# 2015_CONNECTEUR_BALISE.net
KiCad netlist of a schematic drawn in Altium Designer
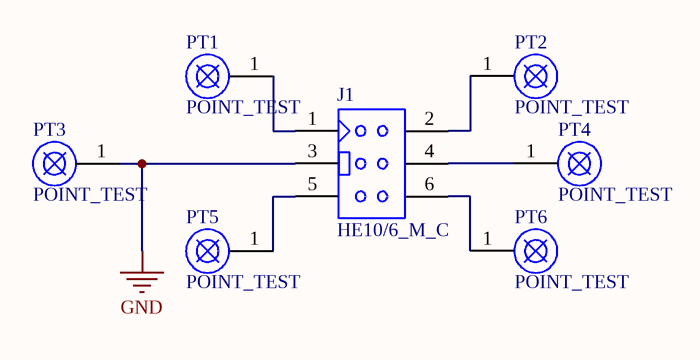
[diagram p0: 2015_CONNECTEUR_BALISE.SchDoc]

(export (version "E")
  (design (tool "Eeschema 10.0.6"))
  (components
    (comp (ref "J1")
      (value "HE10/6_MALE_COUDE")
      (footprint "HE10/6_M_C")
      (description "EMBASE HE10/6 MALE COUDE")
      (fields (field (name "TYPE") "HE10/6_M_C"))
      (libsource (lib "connecteurs") (part "HE10/6_MALE_COUDE"))
    )
    (comp (ref "PT1")
      (value "POINT_TEST")
      (footprint "POINT_TEST")
      (description "POINT TEST")
      (libsource (lib "connecteurs") (part "POINT_TEST"))
    )
    (comp (ref "PT2")
      (value "POINT_TEST")
      (footprint "POINT_TEST")
      (description "POINT TEST")
      (libsource (lib "connecteurs") (part "POINT_TEST"))
    )
    (comp (ref "PT3")
      (value "POINT_TEST")
      (footprint "POINT_TEST")
      (description "POINT TEST")
      (libsource (lib "connecteurs") (part "POINT_TEST"))
    )
    (comp (ref "PT4")
      (value "POINT_TEST")
      (footprint "POINT_TEST")
      (description "POINT TEST")
      (libsource (lib "connecteurs") (part "POINT_TEST"))
    )
    (comp (ref "PT5")
      (value "POINT_TEST")
      (footprint "POINT_TEST")
      (description "POINT TEST")
      (libsource (lib "connecteurs") (part "POINT_TEST"))
    )
    (comp (ref "PT6")
      (value "POINT_TEST")
      (footprint "POINT_TEST")
      (description "POINT TEST")
      (libsource (lib "connecteurs") (part "POINT_TEST"))
    )
  )
  (nets
    (net (code "1") (name "GND") (class "Default")
      (node (ref "J1") (pin "3") (pinfunction "3_3") (pintype "passive"))
      (node (ref "PT3") (pin "1") (pinfunction "3_1") (pintype "passive"))
    )
    (net (code "2") (name "Net-(PT1-3)") (class "Default")
      (node (ref "J1") (pin "1") (pinfunction "1_1") (pintype "passive"))
      (node (ref "PT1") (pin "1") (pinfunction "3_1") (pintype "passive"))
    )
    (net (code "3") (name "Net-(PT2-3)") (class "Default")
      (node (ref "J1") (pin "2") (pinfunction "2_2") (pintype "passive"))
      (node (ref "PT2") (pin "1") (pinfunction "3_1") (pintype "passive"))
    )
    (net (code "4") (name "Net-(PT4-3)") (class "Default")
      (node (ref "J1") (pin "4") (pinfunction "4_4") (pintype "passive"))
      (node (ref "PT4") (pin "1") (pinfunction "3_1") (pintype "passive"))
    )
    (net (code "5") (name "Net-(PT5-3)") (class "Default")
      (node (ref "J1") (pin "5") (pinfunction "5_5") (pintype "passive"))
      (node (ref "PT5") (pin "1") (pinfunction "3_1") (pintype "passive"))
    )
    (net (code "6") (name "Net-(PT6-3)") (class "Default")
      (node (ref "J1") (pin "6") (pinfunction "6_6") (pintype "passive"))
      (node (ref "PT6") (pin "1") (pinfunction "3_1") (pintype "passive"))
    )
  )
)
